# ad724pal.net
KiCad netlist of a schematic drawn in EAGLE
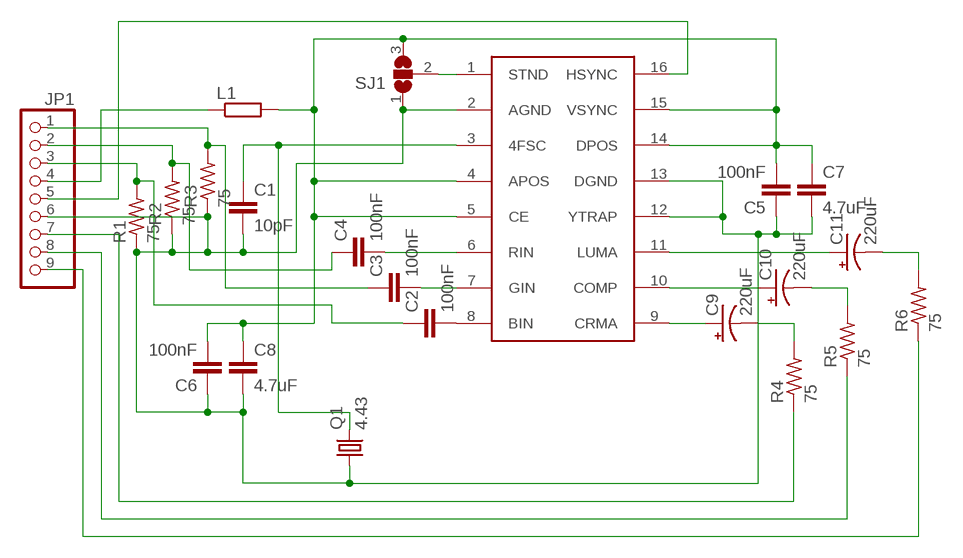
[diagram p0: schematic, sheet 1]

(export (version "E")
  (design (tool "Eeschema 10.0.6"))
  (components
    (comp (ref "C1")
      (value "10pF")
      (footprint "eagle-import:C0805")
      (libsource (lib "eagle-import") (part "C-EUC0805"))
    )
    (comp (ref "C2")
      (value "100nF")
      (footprint "eagle-import:C0603")
      (libsource (lib "eagle-import") (part "C-EUC0603"))
    )
    (comp (ref "C3")
      (value "100nF")
      (footprint "eagle-import:C0603")
      (libsource (lib "eagle-import") (part "C-EUC0603"))
    )
    (comp (ref "C4")
      (value "100nF")
      (footprint "eagle-import:C0603")
      (libsource (lib "eagle-import") (part "C-EUC0603"))
    )
    (comp (ref "C5")
      (value "100nF")
      (footprint "eagle-import:C0603")
      (libsource (lib "eagle-import") (part "C-EUC0603"))
    )
    (comp (ref "C6")
      (value "100nF")
      (footprint "eagle-import:C0603")
      (libsource (lib "eagle-import") (part "C-EUC0603"))
    )
    (comp (ref "C7")
      (value "4.7uF")
      (footprint "eagle-import:C0805")
      (libsource (lib "eagle-import") (part "C-EUC0805"))
    )
    (comp (ref "C8")
      (value "4.7uF")
      (footprint "eagle-import:C0805")
      (libsource (lib "eagle-import") (part "C-EUC0805"))
    )
    (comp (ref "C9")
      (value "220uF")
      (footprint "eagle-import:E2,5-6")
      (libsource (lib "eagle-import") (part "CPOL-USE2.5-6"))
    )
    (comp (ref "C10")
      (value "220uF")
      (footprint "eagle-import:E2,5-6")
      (libsource (lib "eagle-import") (part "CPOL-USE2.5-6"))
    )
    (comp (ref "C11")
      (value "220uF")
      (footprint "eagle-import:E2,5-6")
      (libsource (lib "eagle-import") (part "CPOL-USE2.5-6"))
    )
    (comp (ref "JP1")
      (value "PINHD-1X9")
      (footprint "eagle-import:1X09")
      (libsource (lib "eagle-import") (part "PINHD-1X9"))
    )
    (comp (ref "L1")
      (value "R-EU_R0805")
      (footprint "eagle-import:R0805")
      (libsource (lib "eagle-import") (part "R-EU_R0805"))
    )
    (comp (ref "Q1")
      (value "4.43")
      (footprint "eagle-import:HC49_S")
      (libsource (lib "eagle-import") (part "CRYSTALHC49S"))
    )
    (comp (ref "R1")
      (value "75")
      (footprint "eagle-import:R0805")
      (libsource (lib "eagle-import") (part "R-US_R0805"))
    )
    (comp (ref "R2")
      (value "75")
      (footprint "eagle-import:R0805")
      (libsource (lib "eagle-import") (part "R-US_R0805"))
    )
    (comp (ref "R3")
      (value "75")
      (footprint "eagle-import:R0805")
      (libsource (lib "eagle-import") (part "R-US_R0805"))
    )
    (comp (ref "R4")
      (value "75")
      (footprint "eagle-import:R0805")
      (libsource (lib "eagle-import") (part "R-US_R0805"))
    )
    (comp (ref "R5")
      (value "75")
      (footprint "eagle-import:R0805")
      (libsource (lib "eagle-import") (part "R-US_R0805"))
    )
    (comp (ref "R6")
      (value "75")
      (footprint "eagle-import:R0805")
      (libsource (lib "eagle-import") (part "R-US_R0805"))
    )
    (comp (ref "SJ1")
      (value "SJ2W")
      (footprint "eagle-import:SJ_2")
      (libsource (lib "eagle-import") (part "SJ2W"))
    )
    (comp (ref "U1")
      (value "AD725")
      (footprint "eagle-import:SO16W")
      (libsource (lib "eagle-import") (part "AD725"))
    )
  )
  (nets
    (net (code "1") (name "Net-(C2-Pad1)") (class "Default")
      (node (ref "C2") (pin "1") (pinfunction "1_1") (pintype "passive"))
      (node (ref "JP1") (pin "3") (pinfunction "3_3") (pintype "passive"))
      (node (ref "R1") (pin "2") (pinfunction "2_2") (pintype "passive"))
    )
    (net (code "2") (name "Net-(C3-Pad1)") (class "Default")
      (node (ref "C3") (pin "1") (pinfunction "1_1") (pintype "passive"))
      (node (ref "JP1") (pin "1") (pinfunction "1_1") (pintype "passive"))
      (node (ref "R3") (pin "2") (pinfunction "2_2") (pintype "passive"))
    )
    (net (code "3") (name "Net-(C4-Pad1)") (class "Default")
      (node (ref "C4") (pin "1") (pinfunction "1_1") (pintype "passive"))
      (node (ref "JP1") (pin "2") (pinfunction "2_2") (pintype "passive"))
      (node (ref "R2") (pin "2") (pinfunction "2_2") (pintype "passive"))
    )
    (net (code "4") (name "Net-(C9-Pad-)") (class "Default")
      (node (ref "C9") (pin "-") (pinfunction "-_-") (pintype "passive"))
      (node (ref "R4") (pin "2") (pinfunction "2_2") (pintype "passive"))
    )
    (net (code "5") (name "Net-(C10-Pad-)") (class "Default")
      (node (ref "C10") (pin "-") (pinfunction "-_-") (pintype "passive"))
      (node (ref "R5") (pin "2") (pinfunction "2_2") (pintype "passive"))
    )
    (net (code "6") (name "Net-(C11-Pad-)") (class "Default")
      (node (ref "C11") (pin "-") (pinfunction "-_-") (pintype "passive"))
      (node (ref "R6") (pin "2") (pinfunction "2_2") (pintype "passive"))
    )
    (net (code "7") (name "Net-(JP1-Pad4)") (class "Default")
      (node (ref "JP1") (pin "4") (pinfunction "4_4") (pintype "passive"))
      (node (ref "L1") (pin "1") (pinfunction "1_1") (pintype "passive"))
    )
    (net (code "8") (name "Net-(JP1-Pad7)") (class "Default")
      (node (ref "JP1") (pin "7") (pinfunction "7_7") (pintype "passive"))
      (node (ref "R4") (pin "1") (pinfunction "1_1") (pintype "passive"))
    )
    (net (code "9") (name "Net-(JP1-Pad8)") (class "Default")
      (node (ref "JP1") (pin "8") (pinfunction "8_8") (pintype "passive"))
      (node (ref "R5") (pin "1") (pinfunction "1_1") (pintype "passive"))
    )
    (net (code "10") (name "Net-(JP1-Pad9)") (class "Default")
      (node (ref "JP1") (pin "9") (pinfunction "9_9") (pintype "passive"))
      (node (ref "R6") (pin "1") (pinfunction "1_1") (pintype "passive"))
    )
    (net (code "11") (name "Net-(U1-4FSC)") (class "Default")
      (node (ref "C1") (pin "1") (pinfunction "1_1") (pintype "passive"))
      (node (ref "Q1") (pin "2") (pinfunction "2_2") (pintype "passive"))
      (node (ref "U1") (pin "3") (pinfunction "4FSC_3") (pintype "bidirectional"))
    )
    (net (code "12") (name "Net-(U1-AGND)") (class "Default")
      (node (ref "C1") (pin "2") (pinfunction "2_2") (pintype "passive"))
      (node (ref "C5") (pin "1") (pinfunction "1_1") (pintype "passive"))
      (node (ref "C6") (pin "1") (pinfunction "1_1") (pintype "passive"))
      (node (ref "C7") (pin "2") (pinfunction "2_2") (pintype "passive"))
      (node (ref "C8") (pin "2") (pinfunction "2_2") (pintype "passive"))
      (node (ref "JP1") (pin "6") (pinfunction "6_6") (pintype "passive"))
      (node (ref "Q1") (pin "1") (pinfunction "1_1") (pintype "passive"))
      (node (ref "R1") (pin "1") (pinfunction "1_1") (pintype "passive"))
      (node (ref "R2") (pin "1") (pinfunction "1_1") (pintype "passive"))
      (node (ref "R3") (pin "1") (pinfunction "1_1") (pintype "passive"))
      (node (ref "SJ1") (pin "1") (pinfunction "1_1") (pintype "passive"))
      (node (ref "U1") (pin "12") (pinfunction "YTRAP_12") (pintype "bidirectional"))
      (node (ref "U1") (pin "13") (pinfunction "DGND_13") (pintype "bidirectional"))
      (node (ref "U1") (pin "2") (pinfunction "AGND_2") (pintype "bidirectional"))
    )
    (net (code "13") (name "Net-(U1-APOS)") (class "Default")
      (node (ref "C5") (pin "2") (pinfunction "2_2") (pintype "passive"))
      (node (ref "C6") (pin "2") (pinfunction "2_2") (pintype "passive"))
      (node (ref "C7") (pin "1") (pinfunction "1_1") (pintype "passive"))
      (node (ref "C8") (pin "1") (pinfunction "1_1") (pintype "passive"))
      (node (ref "L1") (pin "2") (pinfunction "2_2") (pintype "passive"))
      (node (ref "SJ1") (pin "3") (pinfunction "3_3") (pintype "passive"))
      (node (ref "U1") (pin "14") (pinfunction "DPOS_14") (pintype "bidirectional"))
      (node (ref "U1") (pin "15") (pinfunction "VSYNC_15") (pintype "bidirectional"))
      (node (ref "U1") (pin "4") (pinfunction "APOS_4") (pintype "bidirectional"))
      (node (ref "U1") (pin "5") (pinfunction "CE_5") (pintype "bidirectional"))
    )
    (net (code "14") (name "Net-(U1-BIN)") (class "Default")
      (node (ref "C2") (pin "2") (pinfunction "2_2") (pintype "passive"))
      (node (ref "U1") (pin "8") (pinfunction "BIN_8") (pintype "bidirectional"))
    )
    (net (code "15") (name "Net-(U1-COMP)") (class "Default")
      (node (ref "C10") (pin "+") (pinfunction "+_+") (pintype "passive"))
      (node (ref "U1") (pin "10") (pinfunction "COMP_10") (pintype "bidirectional"))
    )
    (net (code "16") (name "Net-(U1-CRMA)") (class "Default")
      (node (ref "C9") (pin "+") (pinfunction "+_+") (pintype "passive"))
      (node (ref "U1") (pin "9") (pinfunction "CRMA_9") (pintype "bidirectional"))
    )
    (net (code "17") (name "Net-(U1-GIN)") (class "Default")
      (node (ref "C3") (pin "2") (pinfunction "2_2") (pintype "passive"))
      (node (ref "U1") (pin "7") (pinfunction "GIN_7") (pintype "bidirectional"))
    )
    (net (code "18") (name "Net-(U1-HSYNC)") (class "Default")
      (node (ref "JP1") (pin "5") (pinfunction "5_5") (pintype "passive"))
      (node (ref "U1") (pin "16") (pinfunction "HSYNC_16") (pintype "bidirectional"))
    )
    (net (code "19") (name "Net-(U1-LUMA)") (class "Default")
      (node (ref "C11") (pin "+") (pinfunction "+_+") (pintype "passive"))
      (node (ref "U1") (pin "11") (pinfunction "LUMA_11") (pintype "bidirectional"))
    )
    (net (code "20") (name "Net-(U1-RIN)") (class "Default")
      (node (ref "C4") (pin "2") (pinfunction "2_2") (pintype "passive"))
      (node (ref "U1") (pin "6") (pinfunction "RIN_6") (pintype "bidirectional"))
    )
    (net (code "21") (name "Net-(U1-STND)") (class "Default")
      (node (ref "SJ1") (pin "2") (pinfunction "2_2") (pintype "passive"))
      (node (ref "U1") (pin "1") (pinfunction "STND_1") (pintype "bidirectional"))
    )
  )
)
